# wemos_d1_grove_qwiic_v11sch.net
KiCad netlist of a schematic drawn in EAGLE
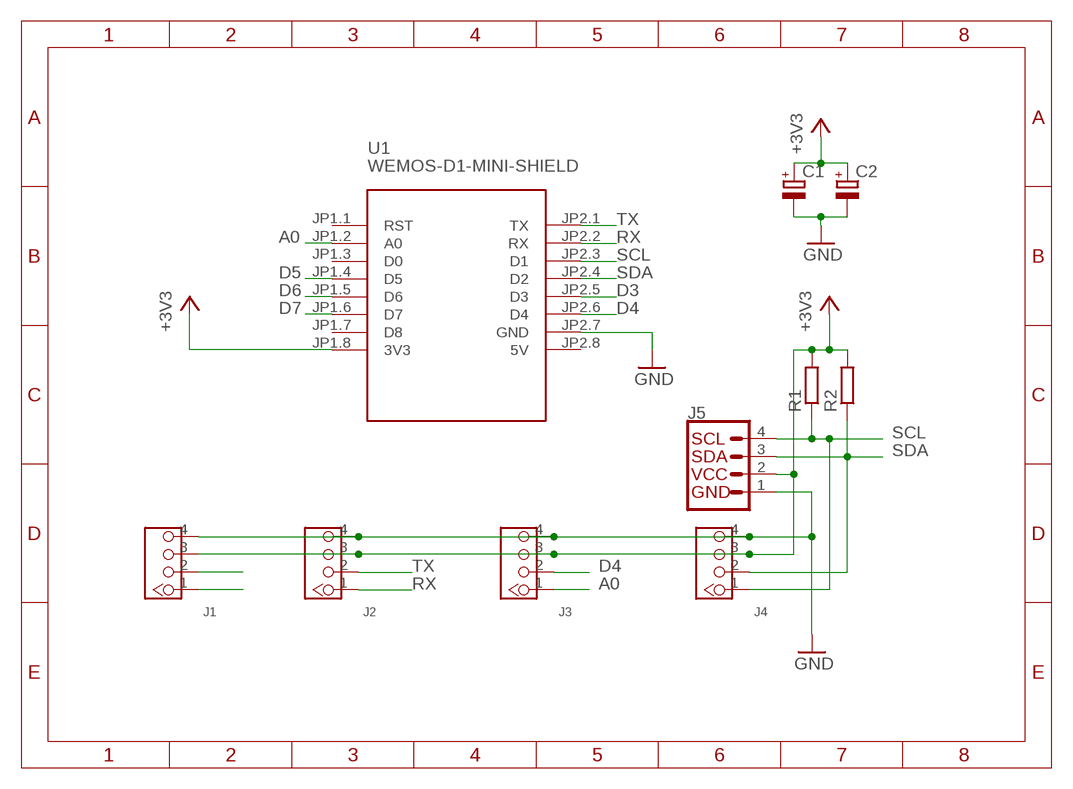
[diagram p0: schematic, sheet 1]

(export (version "E")
  (design (tool "Eeschema 10.0.6"))
  (components
    (comp (ref "C1")
      (value "CPOL-EU153CLV-0505")
      (footprint "eagle-import:153CLV-0505")
      (libsource (lib "eagle-import") (part "CPOL-EU153CLV-0505"))
    )
    (comp (ref "C2")
      (value "CPOL-EUCT3528")
      (footprint "eagle-import:CT3528")
      (libsource (lib "eagle-import") (part "CPOL-EUCT3528"))
    )
    (comp (ref "J1")
      (value "4P-2.0")
      (footprint "eagle-import:HW4-2.0")
      (libsource (lib "eagle-import") (part "GROVE-CONNECTOR-DIP(4P-2.0)"))
    )
    (comp (ref "J2")
      (value "4P-2.0")
      (footprint "eagle-import:HW4-2.0")
      (libsource (lib "eagle-import") (part "GROVE-CONNECTOR-DIP(4P-2.0)"))
    )
    (comp (ref "J3")
      (value "4P-2.0")
      (footprint "eagle-import:HW4-2.0")
      (libsource (lib "eagle-import") (part "GROVE-CONNECTOR-DIP(4P-2.0)"))
    )
    (comp (ref "J4")
      (value "4P-2.0")
      (footprint "eagle-import:HW4-2.0")
      (libsource (lib "eagle-import") (part "GROVE-CONNECTOR-DIP(4P-2.0)"))
    )
    (comp (ref "J5")
      (value "QWIIC_CONNECTORJS-1MM")
      (footprint "eagle-import:1X04_1MM_RA")
      (libsource (lib "eagle-import") (part "QWIIC_CONNECTORJS-1MM"))
    )
    (comp (ref "R1")
      (value "R-EU_R0603")
      (footprint "eagle-import:R0603")
      (libsource (lib "eagle-import") (part "R-EU_R0603"))
    )
    (comp (ref "R2")
      (value "R-EU_R0603")
      (footprint "eagle-import:R0603")
      (libsource (lib "eagle-import") (part "R-EU_R0603"))
    )
    (comp (ref "U1")
      (value "WEMOS-D1-MINI-SHIELD")
      (footprint "eagle-import:WEMOS-D1-MINI-SHIELD")
      (libsource (lib "eagle-import") (part "WEMOS-D1-MINI-SHIELD"))
    )
  )
  (nets
    (net (code "1") (name "+3V3") (class "Default")
      (node (ref "C1") (pin "+") (pinfunction "+_+") (pintype "passive"))
      (node (ref "C2") (pin "+") (pinfunction "+_+") (pintype "passive"))
      (node (ref "J1") (pin "3") (pinfunction "3_3") (pintype "bidirectional"))
      (node (ref "J2") (pin "3") (pinfunction "3_3") (pintype "bidirectional"))
      (node (ref "J3") (pin "3") (pinfunction "3_3") (pintype "bidirectional"))
      (node (ref "J4") (pin "3") (pinfunction "3_3") (pintype "bidirectional"))
      (node (ref "J5") (pin "2") (pinfunction "VCC_2") (pintype "power_in"))
      (node (ref "R1") (pin "2") (pinfunction "2_2") (pintype "passive"))
      (node (ref "R2") (pin "2") (pinfunction "2_2") (pintype "passive"))
      (node (ref "U1") (pin "JP1.8") (pinfunction "3V3_JP1.8") (pintype "power_in"))
    )
    (net (code "2") (name "/5V") (class "Default")
      (node (ref "U1") (pin "JP2.8") (pinfunction "5V_JP2.8") (pintype "power_in"))
    )
    (net (code "3") (name "/A0") (class "Default")
      (node (ref "J3") (pin "1") (pinfunction "1_1") (pintype "bidirectional"))
      (node (ref "U1") (pin "JP1.2") (pinfunction "A0_JP1.2") (pintype "bidirectional"))
    )
    (net (code "4") (name "/D3") (class "Default")
      (node (ref "U1") (pin "JP2.5") (pinfunction "D3_JP2.5") (pintype "bidirectional"))
    )
    (net (code "5") (name "/D4") (class "Default")
      (node (ref "J3") (pin "2") (pinfunction "2_2") (pintype "bidirectional"))
      (node (ref "U1") (pin "JP2.6") (pinfunction "D4_JP2.6") (pintype "bidirectional"))
    )
    (net (code "6") (name "/D5") (class "Default")
      (node (ref "J1") (pin "1") (pinfunction "1_1") (pintype "bidirectional"))
      (node (ref "U1") (pin "JP1.4") (pinfunction "D5_JP1.4") (pintype "bidirectional"))
    )
    (net (code "7") (name "/D6") (class "Default")
      (node (ref "J1") (pin "2") (pinfunction "2_2") (pintype "bidirectional"))
      (node (ref "U1") (pin "JP1.5") (pinfunction "D6_JP1.5") (pintype "bidirectional"))
    )
    (net (code "8") (name "/D7") (class "Default")
      (node (ref "U1") (pin "JP1.6") (pinfunction "D7_JP1.6") (pintype "bidirectional"))
    )
    (net (code "9") (name "/RX") (class "Default")
      (node (ref "J2") (pin "1") (pinfunction "1_1") (pintype "bidirectional"))
      (node (ref "U1") (pin "JP2.2") (pinfunction "RX_JP2.2") (pintype "bidirectional"))
    )
    (net (code "10") (name "/SCL") (class "Default")
      (node (ref "J4") (pin "1") (pinfunction "1_1") (pintype "bidirectional"))
      (node (ref "J5") (pin "4") (pinfunction "SCL_4") (pintype "passive"))
      (node (ref "R1") (pin "1") (pinfunction "1_1") (pintype "passive"))
      (node (ref "U1") (pin "JP2.3") (pinfunction "D1_JP2.3") (pintype "bidirectional"))
    )
    (net (code "11") (name "/SDA") (class "Default")
      (node (ref "J4") (pin "2") (pinfunction "2_2") (pintype "bidirectional"))
      (node (ref "J5") (pin "3") (pinfunction "SDA_3") (pintype "passive"))
      (node (ref "R2") (pin "1") (pinfunction "1_1") (pintype "passive"))
      (node (ref "U1") (pin "JP2.4") (pinfunction "D2_JP2.4") (pintype "bidirectional"))
    )
    (net (code "12") (name "/TX") (class "Default")
      (node (ref "J2") (pin "2") (pinfunction "2_2") (pintype "bidirectional"))
      (node (ref "U1") (pin "JP2.1") (pinfunction "TX_JP2.1") (pintype "bidirectional"))
    )
    (net (code "13") (name "GND") (class "Default")
      (node (ref "C1") (pin "-") (pinfunction "-_-") (pintype "passive"))
      (node (ref "C2") (pin "-") (pinfunction "-_-") (pintype "passive"))
      (node (ref "J1") (pin "4") (pinfunction "4_4") (pintype "bidirectional"))
      (node (ref "J2") (pin "4") (pinfunction "4_4") (pintype "bidirectional"))
      (node (ref "J3") (pin "4") (pinfunction "4_4") (pintype "bidirectional"))
      (node (ref "J4") (pin "4") (pinfunction "4_4") (pintype "bidirectional"))
      (node (ref "J5") (pin "1") (pinfunction "GND_1") (pintype "power_in"))
      (node (ref "U1") (pin "JP2.7") (pinfunction "GND_JP2.7") (pintype "power_in"))
    )
    (net (code "14") (name "unconnected-(U1-D0-PadJP1.3)") (class "Default")
      (node (ref "U1") (pin "JP1.3") (pinfunction "D0_JP1.3") (pintype "bidirectional"))
    )
    (net (code "15") (name "unconnected-(U1-D8-PadJP1.7)") (class "Default")
      (node (ref "U1") (pin "JP1.7") (pinfunction "D8_JP1.7") (pintype "bidirectional"))
    )
    (net (code "16") (name "unconnected-(U1-RST-PadJP1.1)") (class "Default")
      (node (ref "U1") (pin "JP1.1") (pinfunction "RST_JP1.1") (pintype "bidirectional"))
    )
  )
)
